# 16ch_omn_hirose_adapter_400mil.net
KiCad netlist of a schematic drawn in EAGLE
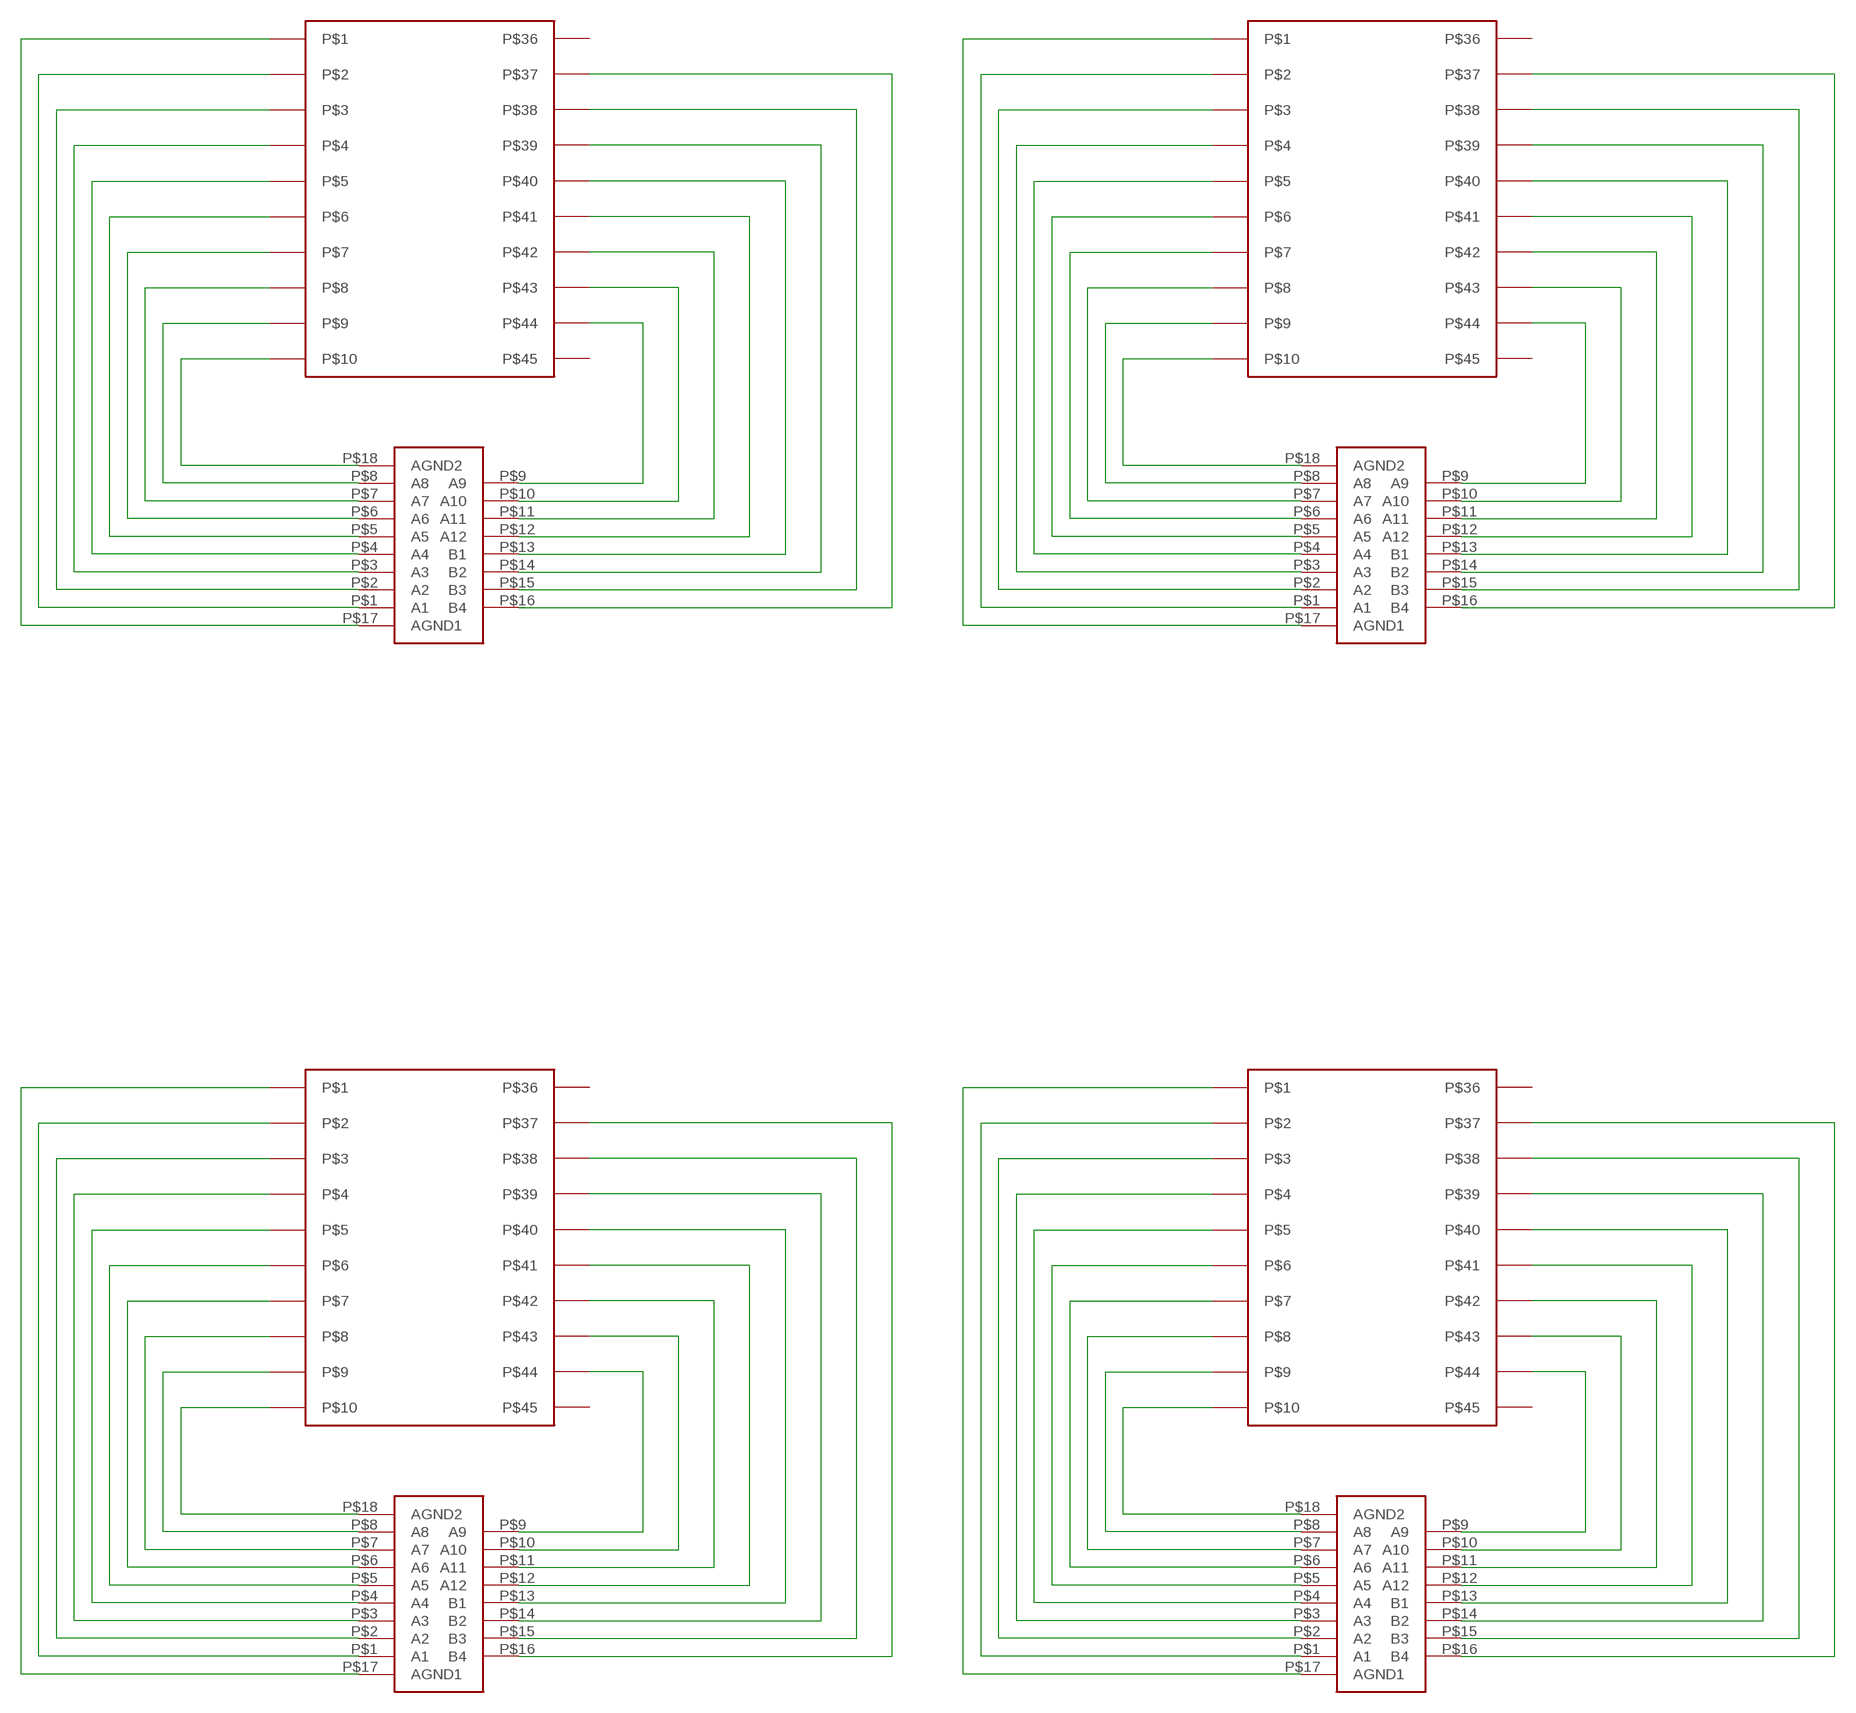
[diagram p0: schematic, sheet 1]

(export (version "E")
  (design (tool "Eeschema 10.0.6"))
  (components
    (comp (ref "U$1")
      (value "HIROSE_DF40_70PIN")
      (footprint "eagle-import:HIROSE_DF40C-70DS")
      (libsource (lib "eagle-import") (part "HIROSE_DF40_70PIN"))
    )
    (comp (ref "U$2")
      (value "OMNETICS_FE18")
      (footprint "eagle-import:OMNETICS_FE18")
      (libsource (lib "eagle-import") (part "OMNETICS_FE18"))
    )
    (comp (ref "U$3")
      (value "HIROSE_DF40_70PIN")
      (footprint "eagle-import:HIROSE_DF40C-70DS")
      (libsource (lib "eagle-import") (part "HIROSE_DF40_70PIN"))
    )
    (comp (ref "U$4")
      (value "OMNETICS_FE18")
      (footprint "eagle-import:OMNETICS_FE18")
      (libsource (lib "eagle-import") (part "OMNETICS_FE18"))
    )
    (comp (ref "U$5")
      (value "HIROSE_DF40_70PIN")
      (footprint "eagle-import:HIROSE_DF40C-70DS")
      (libsource (lib "eagle-import") (part "HIROSE_DF40_70PIN"))
    )
    (comp (ref "U$6")
      (value "OMNETICS_FE18")
      (footprint "eagle-import:OMNETICS_FE18")
      (libsource (lib "eagle-import") (part "OMNETICS_FE18"))
    )
    (comp (ref "U$7")
      (value "HIROSE_DF40_70PIN")
      (footprint "eagle-import:HIROSE_DF40C-70DS")
      (libsource (lib "eagle-import") (part "HIROSE_DF40_70PIN"))
    )
    (comp (ref "U$8")
      (value "OMNETICS_FE18")
      (footprint "eagle-import:OMNETICS_FE18")
      (libsource (lib "eagle-import") (part "OMNETICS_FE18"))
    )
  )
  (nets
    (net (code "1") (name "Net-(U$2-A1)") (class "Default")
      (node (ref "U$1") (pin "P$2") (pinfunction "P$2_P$2") (pintype "bidirectional"))
      (node (ref "U$2") (pin "P$1") (pinfunction "A1_P$1") (pintype "bidirectional"))
    )
    (net (code "2") (name "Net-(U$2-A2)") (class "Default")
      (node (ref "U$1") (pin "P$3") (pinfunction "P$3_P$3") (pintype "bidirectional"))
      (node (ref "U$2") (pin "P$2") (pinfunction "A2_P$2") (pintype "bidirectional"))
    )
    (net (code "3") (name "Net-(U$2-A3)") (class "Default")
      (node (ref "U$1") (pin "P$4") (pinfunction "P$4_P$4") (pintype "bidirectional"))
      (node (ref "U$2") (pin "P$3") (pinfunction "A3_P$3") (pintype "bidirectional"))
    )
    (net (code "4") (name "Net-(U$2-A4)") (class "Default")
      (node (ref "U$1") (pin "P$5") (pinfunction "P$5_P$5") (pintype "bidirectional"))
      (node (ref "U$2") (pin "P$4") (pinfunction "A4_P$4") (pintype "bidirectional"))
    )
    (net (code "5") (name "Net-(U$2-A5)") (class "Default")
      (node (ref "U$1") (pin "P$6") (pinfunction "P$6_P$6") (pintype "bidirectional"))
      (node (ref "U$2") (pin "P$5") (pinfunction "A5_P$5") (pintype "bidirectional"))
    )
    (net (code "6") (name "Net-(U$2-A6)") (class "Default")
      (node (ref "U$1") (pin "P$7") (pinfunction "P$7_P$7") (pintype "bidirectional"))
      (node (ref "U$2") (pin "P$6") (pinfunction "A6_P$6") (pintype "bidirectional"))
    )
    (net (code "7") (name "Net-(U$2-A7)") (class "Default")
      (node (ref "U$1") (pin "P$8") (pinfunction "P$8_P$8") (pintype "bidirectional"))
      (node (ref "U$2") (pin "P$7") (pinfunction "A7_P$7") (pintype "bidirectional"))
    )
    (net (code "8") (name "Net-(U$2-A8)") (class "Default")
      (node (ref "U$1") (pin "P$9") (pinfunction "P$9_P$9") (pintype "bidirectional"))
      (node (ref "U$2") (pin "P$8") (pinfunction "A8_P$8") (pintype "bidirectional"))
    )
    (net (code "9") (name "Net-(U$2-A9)") (class "Default")
      (node (ref "U$1") (pin "P$44") (pinfunction "P$44_P$44") (pintype "bidirectional"))
      (node (ref "U$2") (pin "P$9") (pinfunction "A9_P$9") (pintype "bidirectional"))
    )
    (net (code "10") (name "Net-(U$2-A10)") (class "Default")
      (node (ref "U$1") (pin "P$43") (pinfunction "P$43_P$43") (pintype "bidirectional"))
      (node (ref "U$2") (pin "P$10") (pinfunction "A10_P$10") (pintype "bidirectional"))
    )
    (net (code "11") (name "Net-(U$2-A11)") (class "Default")
      (node (ref "U$1") (pin "P$42") (pinfunction "P$42_P$42") (pintype "bidirectional"))
      (node (ref "U$2") (pin "P$11") (pinfunction "A11_P$11") (pintype "bidirectional"))
    )
    (net (code "12") (name "Net-(U$2-A12)") (class "Default")
      (node (ref "U$1") (pin "P$41") (pinfunction "P$41_P$41") (pintype "bidirectional"))
      (node (ref "U$2") (pin "P$12") (pinfunction "A12_P$12") (pintype "bidirectional"))
    )
    (net (code "13") (name "Net-(U$2-AGND1)") (class "Default")
      (node (ref "U$1") (pin "P$1") (pinfunction "P$1_P$1") (pintype "bidirectional"))
      (node (ref "U$2") (pin "P$17") (pinfunction "AGND1_P$17") (pintype "bidirectional"))
    )
    (net (code "14") (name "Net-(U$2-AGND2)") (class "Default")
      (node (ref "U$1") (pin "P$10") (pinfunction "P$10_P$10") (pintype "bidirectional"))
      (node (ref "U$2") (pin "P$18") (pinfunction "AGND2_P$18") (pintype "bidirectional"))
    )
    (net (code "15") (name "Net-(U$2-B1)") (class "Default")
      (node (ref "U$1") (pin "P$40") (pinfunction "P$40_P$40") (pintype "bidirectional"))
      (node (ref "U$2") (pin "P$13") (pinfunction "B1_P$13") (pintype "bidirectional"))
    )
    (net (code "16") (name "Net-(U$2-B2)") (class "Default")
      (node (ref "U$1") (pin "P$39") (pinfunction "P$39_P$39") (pintype "bidirectional"))
      (node (ref "U$2") (pin "P$14") (pinfunction "B2_P$14") (pintype "bidirectional"))
    )
    (net (code "17") (name "Net-(U$2-B3)") (class "Default")
      (node (ref "U$1") (pin "P$38") (pinfunction "P$38_P$38") (pintype "bidirectional"))
      (node (ref "U$2") (pin "P$15") (pinfunction "B3_P$15") (pintype "bidirectional"))
    )
    (net (code "18") (name "Net-(U$2-B4)") (class "Default")
      (node (ref "U$1") (pin "P$37") (pinfunction "P$37_P$37") (pintype "bidirectional"))
      (node (ref "U$2") (pin "P$16") (pinfunction "B4_P$16") (pintype "bidirectional"))
    )
    (net (code "19") (name "Net-(U$4-A1)") (class "Default")
      (node (ref "U$3") (pin "P$2") (pinfunction "P$2_P$2") (pintype "bidirectional"))
      (node (ref "U$4") (pin "P$1") (pinfunction "A1_P$1") (pintype "bidirectional"))
    )
    (net (code "20") (name "Net-(U$4-A2)") (class "Default")
      (node (ref "U$3") (pin "P$3") (pinfunction "P$3_P$3") (pintype "bidirectional"))
      (node (ref "U$4") (pin "P$2") (pinfunction "A2_P$2") (pintype "bidirectional"))
    )
    (net (code "21") (name "Net-(U$4-A3)") (class "Default")
      (node (ref "U$3") (pin "P$4") (pinfunction "P$4_P$4") (pintype "bidirectional"))
      (node (ref "U$4") (pin "P$3") (pinfunction "A3_P$3") (pintype "bidirectional"))
    )
    (net (code "22") (name "Net-(U$4-A4)") (class "Default")
      (node (ref "U$3") (pin "P$5") (pinfunction "P$5_P$5") (pintype "bidirectional"))
      (node (ref "U$4") (pin "P$4") (pinfunction "A4_P$4") (pintype "bidirectional"))
    )
    (net (code "23") (name "Net-(U$4-A5)") (class "Default")
      (node (ref "U$3") (pin "P$6") (pinfunction "P$6_P$6") (pintype "bidirectional"))
      (node (ref "U$4") (pin "P$5") (pinfunction "A5_P$5") (pintype "bidirectional"))
    )
    (net (code "24") (name "Net-(U$4-A6)") (class "Default")
      (node (ref "U$3") (pin "P$7") (pinfunction "P$7_P$7") (pintype "bidirectional"))
      (node (ref "U$4") (pin "P$6") (pinfunction "A6_P$6") (pintype "bidirectional"))
    )
    (net (code "25") (name "Net-(U$4-A7)") (class "Default")
      (node (ref "U$3") (pin "P$8") (pinfunction "P$8_P$8") (pintype "bidirectional"))
      (node (ref "U$4") (pin "P$7") (pinfunction "A7_P$7") (pintype "bidirectional"))
    )
    (net (code "26") (name "Net-(U$4-A8)") (class "Default")
      (node (ref "U$3") (pin "P$9") (pinfunction "P$9_P$9") (pintype "bidirectional"))
      (node (ref "U$4") (pin "P$8") (pinfunction "A8_P$8") (pintype "bidirectional"))
    )
    (net (code "27") (name "Net-(U$4-A9)") (class "Default")
      (node (ref "U$3") (pin "P$44") (pinfunction "P$44_P$44") (pintype "bidirectional"))
      (node (ref "U$4") (pin "P$9") (pinfunction "A9_P$9") (pintype "bidirectional"))
    )
    (net (code "28") (name "Net-(U$4-A10)") (class "Default")
      (node (ref "U$3") (pin "P$43") (pinfunction "P$43_P$43") (pintype "bidirectional"))
      (node (ref "U$4") (pin "P$10") (pinfunction "A10_P$10") (pintype "bidirectional"))
    )
    (net (code "29") (name "Net-(U$4-A11)") (class "Default")
      (node (ref "U$3") (pin "P$42") (pinfunction "P$42_P$42") (pintype "bidirectional"))
      (node (ref "U$4") (pin "P$11") (pinfunction "A11_P$11") (pintype "bidirectional"))
    )
    (net (code "30") (name "Net-(U$4-A12)") (class "Default")
      (node (ref "U$3") (pin "P$41") (pinfunction "P$41_P$41") (pintype "bidirectional"))
      (node (ref "U$4") (pin "P$12") (pinfunction "A12_P$12") (pintype "bidirectional"))
    )
    (net (code "31") (name "Net-(U$4-AGND1)") (class "Default")
      (node (ref "U$3") (pin "P$1") (pinfunction "P$1_P$1") (pintype "bidirectional"))
      (node (ref "U$4") (pin "P$17") (pinfunction "AGND1_P$17") (pintype "bidirectional"))
    )
    (net (code "32") (name "Net-(U$4-AGND2)") (class "Default")
      (node (ref "U$3") (pin "P$10") (pinfunction "P$10_P$10") (pintype "bidirectional"))
      (node (ref "U$4") (pin "P$18") (pinfunction "AGND2_P$18") (pintype "bidirectional"))
    )
    (net (code "33") (name "Net-(U$4-B1)") (class "Default")
      (node (ref "U$3") (pin "P$40") (pinfunction "P$40_P$40") (pintype "bidirectional"))
      (node (ref "U$4") (pin "P$13") (pinfunction "B1_P$13") (pintype "bidirectional"))
    )
    (net (code "34") (name "Net-(U$4-B2)") (class "Default")
      (node (ref "U$3") (pin "P$39") (pinfunction "P$39_P$39") (pintype "bidirectional"))
      (node (ref "U$4") (pin "P$14") (pinfunction "B2_P$14") (pintype "bidirectional"))
    )
    (net (code "35") (name "Net-(U$4-B3)") (class "Default")
      (node (ref "U$3") (pin "P$38") (pinfunction "P$38_P$38") (pintype "bidirectional"))
      (node (ref "U$4") (pin "P$15") (pinfunction "B3_P$15") (pintype "bidirectional"))
    )
    (net (code "36") (name "Net-(U$4-B4)") (class "Default")
      (node (ref "U$3") (pin "P$37") (pinfunction "P$37_P$37") (pintype "bidirectional"))
      (node (ref "U$4") (pin "P$16") (pinfunction "B4_P$16") (pintype "bidirectional"))
    )
    (net (code "37") (name "Net-(U$6-A1)") (class "Default")
      (node (ref "U$5") (pin "P$2") (pinfunction "P$2_P$2") (pintype "bidirectional"))
      (node (ref "U$6") (pin "P$1") (pinfunction "A1_P$1") (pintype "bidirectional"))
    )
    (net (code "38") (name "Net-(U$6-A2)") (class "Default")
      (node (ref "U$5") (pin "P$3") (pinfunction "P$3_P$3") (pintype "bidirectional"))
      (node (ref "U$6") (pin "P$2") (pinfunction "A2_P$2") (pintype "bidirectional"))
    )
    (net (code "39") (name "Net-(U$6-A3)") (class "Default")
      (node (ref "U$5") (pin "P$4") (pinfunction "P$4_P$4") (pintype "bidirectional"))
      (node (ref "U$6") (pin "P$3") (pinfunction "A3_P$3") (pintype "bidirectional"))
    )
    (net (code "40") (name "Net-(U$6-A4)") (class "Default")
      (node (ref "U$5") (pin "P$5") (pinfunction "P$5_P$5") (pintype "bidirectional"))
      (node (ref "U$6") (pin "P$4") (pinfunction "A4_P$4") (pintype "bidirectional"))
    )
    (net (code "41") (name "Net-(U$6-A5)") (class "Default")
      (node (ref "U$5") (pin "P$6") (pinfunction "P$6_P$6") (pintype "bidirectional"))
      (node (ref "U$6") (pin "P$5") (pinfunction "A5_P$5") (pintype "bidirectional"))
    )
    (net (code "42") (name "Net-(U$6-A6)") (class "Default")
      (node (ref "U$5") (pin "P$7") (pinfunction "P$7_P$7") (pintype "bidirectional"))
      (node (ref "U$6") (pin "P$6") (pinfunction "A6_P$6") (pintype "bidirectional"))
    )
    (net (code "43") (name "Net-(U$6-A7)") (class "Default")
      (node (ref "U$5") (pin "P$8") (pinfunction "P$8_P$8") (pintype "bidirectional"))
      (node (ref "U$6") (pin "P$7") (pinfunction "A7_P$7") (pintype "bidirectional"))
    )
    (net (code "44") (name "Net-(U$6-A8)") (class "Default")
      (node (ref "U$5") (pin "P$9") (pinfunction "P$9_P$9") (pintype "bidirectional"))
      (node (ref "U$6") (pin "P$8") (pinfunction "A8_P$8") (pintype "bidirectional"))
    )
    (net (code "45") (name "Net-(U$6-A9)") (class "Default")
      (node (ref "U$5") (pin "P$44") (pinfunction "P$44_P$44") (pintype "bidirectional"))
      (node (ref "U$6") (pin "P$9") (pinfunction "A9_P$9") (pintype "bidirectional"))
    )
    (net (code "46") (name "Net-(U$6-A10)") (class "Default")
      (node (ref "U$5") (pin "P$43") (pinfunction "P$43_P$43") (pintype "bidirectional"))
      (node (ref "U$6") (pin "P$10") (pinfunction "A10_P$10") (pintype "bidirectional"))
    )
    (net (code "47") (name "Net-(U$6-A11)") (class "Default")
      (node (ref "U$5") (pin "P$42") (pinfunction "P$42_P$42") (pintype "bidirectional"))
      (node (ref "U$6") (pin "P$11") (pinfunction "A11_P$11") (pintype "bidirectional"))
    )
    (net (code "48") (name "Net-(U$6-A12)") (class "Default")
      (node (ref "U$5") (pin "P$41") (pinfunction "P$41_P$41") (pintype "bidirectional"))
      (node (ref "U$6") (pin "P$12") (pinfunction "A12_P$12") (pintype "bidirectional"))
    )
    (net (code "49") (name "Net-(U$6-AGND1)") (class "Default")
      (node (ref "U$5") (pin "P$1") (pinfunction "P$1_P$1") (pintype "bidirectional"))
      (node (ref "U$6") (pin "P$17") (pinfunction "AGND1_P$17") (pintype "bidirectional"))
    )
    (net (code "50") (name "Net-(U$6-AGND2)") (class "Default")
      (node (ref "U$5") (pin "P$10") (pinfunction "P$10_P$10") (pintype "bidirectional"))
      (node (ref "U$6") (pin "P$18") (pinfunction "AGND2_P$18") (pintype "bidirectional"))
    )
    (net (code "51") (name "Net-(U$6-B1)") (class "Default")
      (node (ref "U$5") (pin "P$40") (pinfunction "P$40_P$40") (pintype "bidirectional"))
      (node (ref "U$6") (pin "P$13") (pinfunction "B1_P$13") (pintype "bidirectional"))
    )
    (net (code "52") (name "Net-(U$6-B2)") (class "Default")
      (node (ref "U$5") (pin "P$39") (pinfunction "P$39_P$39") (pintype "bidirectional"))
      (node (ref "U$6") (pin "P$14") (pinfunction "B2_P$14") (pintype "bidirectional"))
    )
    (net (code "53") (name "Net-(U$6-B3)") (class "Default")
      (node (ref "U$5") (pin "P$38") (pinfunction "P$38_P$38") (pintype "bidirectional"))
      (node (ref "U$6") (pin "P$15") (pinfunction "B3_P$15") (pintype "bidirectional"))
    )
    (net (code "54") (name "Net-(U$6-B4)") (class "Default")
      (node (ref "U$5") (pin "P$37") (pinfunction "P$37_P$37") (pintype "bidirectional"))
      (node (ref "U$6") (pin "P$16") (pinfunction "B4_P$16") (pintype "bidirectional"))
    )
    (net (code "55") (name "Net-(U$8-A1)") (class "Default")
      (node (ref "U$7") (pin "P$2") (pinfunction "P$2_P$2") (pintype "bidirectional"))
      (node (ref "U$8") (pin "P$1") (pinfunction "A1_P$1") (pintype "bidirectional"))
    )
    (net (code "56") (name "Net-(U$8-A2)") (class "Default")
      (node (ref "U$7") (pin "P$3") (pinfunction "P$3_P$3") (pintype "bidirectional"))
      (node (ref "U$8") (pin "P$2") (pinfunction "A2_P$2") (pintype "bidirectional"))
    )
    (net (code "57") (name "Net-(U$8-A3)") (class "Default")
      (node (ref "U$7") (pin "P$4") (pinfunction "P$4_P$4") (pintype "bidirectional"))
      (node (ref "U$8") (pin "P$3") (pinfunction "A3_P$3") (pintype "bidirectional"))
    )
    (net (code "58") (name "Net-(U$8-A4)") (class "Default")
      (node (ref "U$7") (pin "P$5") (pinfunction "P$5_P$5") (pintype "bidirectional"))
      (node (ref "U$8") (pin "P$4") (pinfunction "A4_P$4") (pintype "bidirectional"))
    )
    (net (code "59") (name "Net-(U$8-A5)") (class "Default")
      (node (ref "U$7") (pin "P$6") (pinfunction "P$6_P$6") (pintype "bidirectional"))
      (node (ref "U$8") (pin "P$5") (pinfunction "A5_P$5") (pintype "bidirectional"))
    )
    (net (code "60") (name "Net-(U$8-A6)") (class "Default")
      (node (ref "U$7") (pin "P$7") (pinfunction "P$7_P$7") (pintype "bidirectional"))
      (node (ref "U$8") (pin "P$6") (pinfunction "A6_P$6") (pintype "bidirectional"))
    )
    (net (code "61") (name "Net-(U$8-A7)") (class "Default")
      (node (ref "U$7") (pin "P$8") (pinfunction "P$8_P$8") (pintype "bidirectional"))
      (node (ref "U$8") (pin "P$7") (pinfunction "A7_P$7") (pintype "bidirectional"))
    )
    (net (code "62") (name "Net-(U$8-A8)") (class "Default")
      (node (ref "U$7") (pin "P$9") (pinfunction "P$9_P$9") (pintype "bidirectional"))
      (node (ref "U$8") (pin "P$8") (pinfunction "A8_P$8") (pintype "bidirectional"))
    )
    (net (code "63") (name "Net-(U$8-A9)") (class "Default")
      (node (ref "U$7") (pin "P$44") (pinfunction "P$44_P$44") (pintype "bidirectional"))
      (node (ref "U$8") (pin "P$9") (pinfunction "A9_P$9") (pintype "bidirectional"))
    )
    (net (code "64") (name "Net-(U$8-A10)") (class "Default")
      (node (ref "U$7") (pin "P$43") (pinfunction "P$43_P$43") (pintype "bidirectional"))
      (node (ref "U$8") (pin "P$10") (pinfunction "A10_P$10") (pintype "bidirectional"))
    )
    (net (code "65") (name "Net-(U$8-A11)") (class "Default")
      (node (ref "U$7") (pin "P$42") (pinfunction "P$42_P$42") (pintype "bidirectional"))
      (node (ref "U$8") (pin "P$11") (pinfunction "A11_P$11") (pintype "bidirectional"))
    )
    (net (code "66") (name "Net-(U$8-A12)") (class "Default")
      (node (ref "U$7") (pin "P$41") (pinfunction "P$41_P$41") (pintype "bidirectional"))
      (node (ref "U$8") (pin "P$12") (pinfunction "A12_P$12") (pintype "bidirectional"))
    )
    (net (code "67") (name "Net-(U$8-AGND1)") (class "Default")
      (node (ref "U$7") (pin "P$1") (pinfunction "P$1_P$1") (pintype "bidirectional"))
      (node (ref "U$8") (pin "P$17") (pinfunction "AGND1_P$17") (pintype "bidirectional"))
    )
    (net (code "68") (name "Net-(U$8-AGND2)") (class "Default")
      (node (ref "U$7") (pin "P$10") (pinfunction "P$10_P$10") (pintype "bidirectional"))
      (node (ref "U$8") (pin "P$18") (pinfunction "AGND2_P$18") (pintype "bidirectional"))
    )
    (net (code "69") (name "Net-(U$8-B1)") (class "Default")
      (node (ref "U$7") (pin "P$40") (pinfunction "P$40_P$40") (pintype "bidirectional"))
      (node (ref "U$8") (pin "P$13") (pinfunction "B1_P$13") (pintype "bidirectional"))
    )
    (net (code "70") (name "Net-(U$8-B2)") (class "Default")
      (node (ref "U$7") (pin "P$39") (pinfunction "P$39_P$39") (pintype "bidirectional"))
      (node (ref "U$8") (pin "P$14") (pinfunction "B2_P$14") (pintype "bidirectional"))
    )
    (net (code "71") (name "Net-(U$8-B3)") (class "Default")
      (node (ref "U$7") (pin "P$38") (pinfunction "P$38_P$38") (pintype "bidirectional"))
      (node (ref "U$8") (pin "P$15") (pinfunction "B3_P$15") (pintype "bidirectional"))
    )
    (net (code "72") (name "Net-(U$8-B4)") (class "Default")
      (node (ref "U$7") (pin "P$37") (pinfunction "P$37_P$37") (pintype "bidirectional"))
      (node (ref "U$8") (pin "P$16") (pinfunction "B4_P$16") (pintype "bidirectional"))
    )
    (net (code "73") (name "unconnected-(U$1-PadP$36)") (class "Default")
      (node (ref "U$1") (pin "P$36") (pinfunction "P$36_P$36") (pintype "bidirectional"))
    )
    (net (code "74") (name "unconnected-(U$1-PadP$45)") (class "Default")
      (node (ref "U$1") (pin "P$45") (pinfunction "P$45_P$45") (pintype "bidirectional"))
    )
    (net (code "75") (name "unconnected-(U$3-PadP$36)") (class "Default")
      (node (ref "U$3") (pin "P$36") (pinfunction "P$36_P$36") (pintype "bidirectional"))
    )
    (net (code "76") (name "unconnected-(U$3-PadP$45)") (class "Default")
      (node (ref "U$3") (pin "P$45") (pinfunction "P$45_P$45") (pintype "bidirectional"))
    )
    (net (code "77") (name "unconnected-(U$5-PadP$36)") (class "Default")
      (node (ref "U$5") (pin "P$36") (pinfunction "P$36_P$36") (pintype "bidirectional"))
    )
    (net (code "78") (name "unconnected-(U$5-PadP$45)") (class "Default")
      (node (ref "U$5") (pin "P$45") (pinfunction "P$45_P$45") (pintype "bidirectional"))
    )
    (net (code "79") (name "unconnected-(U$7-PadP$36)") (class "Default")
      (node (ref "U$7") (pin "P$36") (pinfunction "P$36_P$36") (pintype "bidirectional"))
    )
    (net (code "80") (name "unconnected-(U$7-PadP$45)") (class "Default")
      (node (ref "U$7") (pin "P$45") (pinfunction "P$45_P$45") (pintype "bidirectional"))
    )
  )
)
